# pca20020_sheet6_environment_sensors.net
KiCad netlist of a schematic drawn in Altium Designer
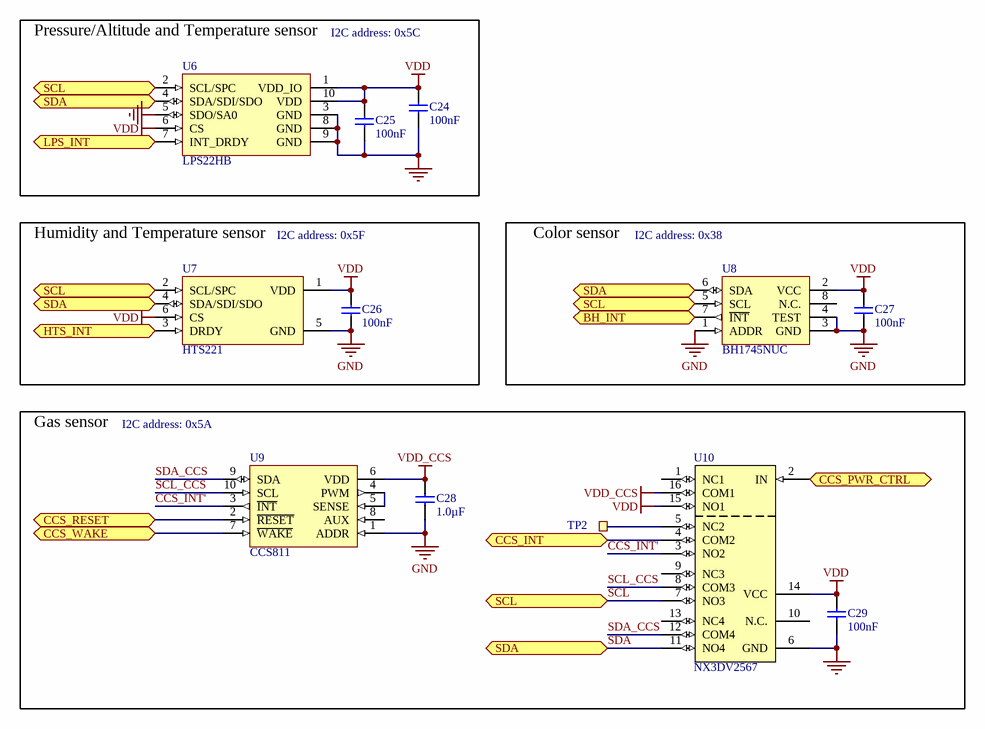
[diagram p0: pca20020_sheet6_environment_sensors.SchDoc]

(export (version "E")
  (design (tool "Eeschema 10.0.6"))
  (components
    (comp (ref "C24")
      (value "100nF")
      (footprint "CAPC1005X04L")
      (description "Capacitor, X7R, ±10%")
      (fields (field (name "PART NUMBER") "C0402-100n") (field (name "PUBLISHER") "Nordic Semiconductor"))
      (libsource (lib "Nordic Passive DB") (part "CAP"))
    )
    (comp (ref "C25")
      (value "100nF")
      (footprint "CAPC1005X04L")
      (description "Capacitor, X7R, ±10%")
      (fields (field (name "PART NUMBER") "C0402-100n") (field (name "PUBLISHER") "Nordic Semiconductor"))
      (libsource (lib "Nordic Passive DB") (part "CAP"))
    )
    (comp (ref "C26")
      (value "100nF")
      (footprint "CAPC1005X04L")
      (description "Capacitor, X7R, ±10%")
      (fields (field (name "PART NUMBER") "C0402-100n") (field (name "PUBLISHER") "Nordic Semiconductor"))
      (libsource (lib "Nordic Passive DB") (part "CAP"))
    )
    (comp (ref "C27")
      (value "100nF")
      (footprint "CAPC1005X04L")
      (description "Capacitor, X7R, ±10%")
      (fields (field (name "PART NUMBER") "C0402-100n") (field (name "PUBLISHER") "Nordic Semiconductor"))
      (libsource (lib "Nordic Passive DB") (part "CAP"))
    )
    (comp (ref "C28")
      (value "1.0µF")
      (footprint "CAPC1005X04L")
      (description "Capacitor, X5R, ±5%, 6.3V")
      (fields (field (name "PART NUMBER") "C0402-1µ0") (field (name "PUBLISHER") "Nordic Semiconductor"))
      (libsource (lib "Nordic Passive DB") (part "CAP"))
    )
    (comp (ref "C29")
      (value "100nF")
      (footprint "CAPC1005X04L")
      (description "Capacitor, X7R, ±10%")
      (fields (field (name "PART NUMBER") "C0402-100n") (field (name "PUBLISHER") "Nordic Semiconductor"))
      (libsource (lib "Nordic Passive DB") (part "CAP"))
    )
    (comp (ref "TP2")
      (value "TP")
      (footprint "TESTPAD-TH")
      (description "Testpoint, through hole")
      (fields (field (name "PART NUMBER") "Testpoint TH") (field (name "PUBLISHER") "Nordic Semiconductor"))
      (libsource (lib "Nordic Passive DB") (part "TESTPAD"))
    )
    (comp (ref "U6")
      (value "LPS22HB")
      (footprint "LGA50P200X200X80-10N")
      (description "MEMS nano pressure sensor: 260-1260 hPa absolute digital output barometer")
      (fields
        (field (name "MANUFACTURER") "STMicroelectronics")
        (field (name "PUBLISHER") "Nordic Semiconductor")
      )
      (libsource (lib "Nordic Active DB") (part "LPS22HB"))
    )
    (comp (ref "U7")
      (value "HTS221")
      (footprint "HLGA100P200X200X100-6N")
      (description "Capacitive digital sensor for relative humidity and temperature")
      (fields
        (field (name "MANUFACTURER") "STMicroelectronics")
        (field (name "PUBLISHER") "Nordic Semiconductor")
      )
      (libsource (lib "Nordic Active DB") (part "HTS221"))
    )
    (comp (ref "U8")
      (value "BH1745NUC")
      (footprint "WSON50P210X210X60_HS-9N")
      (description "Digital 16bit Serial Output Type Color Sensor IC")
      (fields
        (field (name "MANUFACTURER") "Rohm Semiconductor")
        (field (name "PUBLISHER") "Nordic Semiconductor")
      )
      (libsource (lib "Nordic Active DB") (part "BH1745NUC"))
    )
    (comp (ref "U9")
      (value "CCS811")
      (footprint "LGA60P270X400X110_HS-11N")
      (description "Ultra-low power digital gas sensor for monitoring indoor air quality")
      (fields
        (field (name "MANUFACTURER") "Cambridge CMOS Sensors")
        (field (name "PUBLISHER") "Nordic Semiconductor")
      )
      (libsource (lib "Nordic Active DB") (part "CCS811"))
    )
    (comp (ref "U10")
      (value "NX3DV2567")
      (footprint "XQFN40P180X260X50-16N")
      (description "Low-ohmic four-pole double-throw analog switch")
      (fields
        (field (name "PART NUMBER") "NX3DV2567GU")
        (field (name "MANUFACTURER") "NXP Semiconductors")
        (field (name "PUBLISHER") "Nordic Semiconductor")
      )
      (libsource (lib "Nordic Active DB") (part "NX3DV2567"))
    )
  )
  (nets
    (net (code "1") (name "/BH_INT") (class "Default")
      (node (ref "U8") (pin "7") (pinfunction "~{INT}_7") (pintype "output"))
    )
    (net (code "2") (name "/CCS_INT") (class "Default")
      (node (ref "U10") (pin "4") (pinfunction "COM2_4") (pintype "bidirectional"))
    )
    (net (code "3") (name "/CCS_INT'") (class "Default")
      (node (ref "U10") (pin "3") (pinfunction "NO2_3") (pintype "bidirectional"))
      (node (ref "U9") (pin "3") (pinfunction "~{INT}_3") (pintype "output"))
    )
    (net (code "4") (name "/CCS_PWR_CTRL") (class "Default")
      (node (ref "U10") (pin "2") (pinfunction "IN_2") (pintype "input"))
    )
    (net (code "5") (name "/CCS_RESET") (class "Default")
      (node (ref "U9") (pin "2") (pinfunction "~{RESET}_2") (pintype "input"))
    )
    (net (code "6") (name "/CCS_WAKE") (class "Default")
      (node (ref "U9") (pin "7") (pinfunction "~{WAKE}_7") (pintype "input"))
    )
    (net (code "7") (name "/HTS_INT") (class "Default")
      (node (ref "U7") (pin "3") (pinfunction "DRDY_3") (pintype "input"))
    )
    (net (code "8") (name "/LPS_INT") (class "Default")
      (node (ref "U6") (pin "7") (pinfunction "INT_DRDY_7") (pintype "input"))
    )
    (net (code "9") (name "/SCL") (class "Default")
      (node (ref "U10") (pin "7") (pinfunction "NO3_7") (pintype "bidirectional"))
      (node (ref "U6") (pin "2") (pinfunction "SCL/SPC_2") (pintype "input"))
      (node (ref "U7") (pin "2") (pinfunction "SCL/SPC_2") (pintype "input"))
      (node (ref "U8") (pin "5") (pinfunction "SCL_5") (pintype "input"))
    )
    (net (code "10") (name "/SCL_CCS") (class "Default")
      (node (ref "U10") (pin "8") (pinfunction "COM3_8") (pintype "bidirectional"))
      (node (ref "U9") (pin "10") (pinfunction "SCL_10") (pintype "input"))
    )
    (net (code "11") (name "/SDA") (class "Default")
      (node (ref "U10") (pin "11") (pinfunction "NO4_11") (pintype "bidirectional"))
      (node (ref "U6") (pin "4") (pinfunction "SDA/SDI/SDO_4") (pintype "bidirectional"))
      (node (ref "U7") (pin "4") (pinfunction "SDA/SDI/SDO_4") (pintype "bidirectional"))
      (node (ref "U8") (pin "6") (pinfunction "SDA_6") (pintype "bidirectional"))
    )
    (net (code "12") (name "/SDA_CCS") (class "Default")
      (node (ref "U10") (pin "12") (pinfunction "COM4_12") (pintype "bidirectional"))
      (node (ref "U9") (pin "9") (pinfunction "SDA_9") (pintype "bidirectional"))
    )
    (net (code "13") (name "GND") (class "Default")
      (node (ref "C24") (pin "1") (pinfunction "1_1") (pintype "passive"))
      (node (ref "C25") (pin "1") (pinfunction "1_1") (pintype "passive"))
      (node (ref "C26") (pin "1") (pinfunction "1_1") (pintype "passive"))
      (node (ref "C27") (pin "1") (pinfunction "1_1") (pintype "passive"))
      (node (ref "C28") (pin "1") (pinfunction "1_1") (pintype "passive"))
      (node (ref "C29") (pin "1") (pinfunction "1_1") (pintype "passive"))
      (node (ref "U10") (pin "6") (pinfunction "GND_6") (pintype "power_in"))
      (node (ref "U6") (pin "3") (pinfunction "GND_3") (pintype "power_in"))
      (node (ref "U6") (pin "5") (pinfunction "SDO/SA0_5") (pintype "bidirectional"))
      (node (ref "U6") (pin "8") (pinfunction "GND_8") (pintype "power_in"))
      (node (ref "U6") (pin "9") (pinfunction "GND_9") (pintype "power_in"))
      (node (ref "U7") (pin "5") (pinfunction "GND_5") (pintype "power_in"))
      (node (ref "U8") (pin "1") (pinfunction "ADDR_1") (pintype "input"))
      (node (ref "U8") (pin "3") (pinfunction "GND_3") (pintype "power_in"))
      (node (ref "U8") (pin "4") (pinfunction "TEST_4") (pintype "passive"))
      (node (ref "U8") (pin "9") (pinfunction "GND_9") (pintype "power_in"))
      (node (ref "U9") (pin "1") (pinfunction "ADDR_1") (pintype "input"))
      (node (ref "U9") (pin "11") (pinfunction "GND_11") (pintype "power_in"))
    )
    (net (code "14") (name "Net-(U9-PWM)") (class "Default")
      (node (ref "U9") (pin "4") (pinfunction "PWM_4") (pintype "output"))
      (node (ref "U9") (pin "5") (pinfunction "SENSE_5") (pintype "input"))
    )
    (net (code "15") (name "Net-(U10-NC2)") (class "Default")
      (node (ref "TP2") (pin "1") (pinfunction "1_1") (pintype "passive"))
      (node (ref "U10") (pin "5") (pinfunction "NC2_5") (pintype "bidirectional"))
    )
    (net (code "16") (name "VDD") (class "Default")
      (node (ref "C24") (pin "2") (pinfunction "2_2") (pintype "passive"))
      (node (ref "C25") (pin "2") (pinfunction "2_2") (pintype "passive"))
      (node (ref "C26") (pin "2") (pinfunction "2_2") (pintype "passive"))
      (node (ref "C27") (pin "2") (pinfunction "2_2") (pintype "passive"))
      (node (ref "C29") (pin "2") (pinfunction "2_2") (pintype "passive"))
      (node (ref "U10") (pin "14") (pinfunction "VCC_14") (pintype "power_in"))
      (node (ref "U10") (pin "15") (pinfunction "NO1_15") (pintype "bidirectional"))
      (node (ref "U6") (pin "1") (pinfunction "VDD_IO_1") (pintype "power_in"))
      (node (ref "U6") (pin "10") (pinfunction "VDD_10") (pintype "power_in"))
      (node (ref "U6") (pin "6") (pinfunction "CS_6") (pintype "input"))
      (node (ref "U7") (pin "1") (pinfunction "VDD_1") (pintype "power_in"))
      (node (ref "U7") (pin "6") (pinfunction "CS_6") (pintype "input"))
      (node (ref "U8") (pin "2") (pinfunction "VCC_2") (pintype "power_in"))
    )
    (net (code "17") (name "VDD_CCS") (class "Default")
      (node (ref "C28") (pin "2") (pinfunction "2_2") (pintype "passive"))
      (node (ref "U10") (pin "16") (pinfunction "COM1_16") (pintype "bidirectional"))
      (node (ref "U9") (pin "6") (pinfunction "VDD_6") (pintype "power_in"))
    )
    (net (code "18") (name "unconnected-(U8-N.C.-Pad8)") (class "Default")
      (node (ref "U8") (pin "8") (pinfunction "N.C._8") (pintype "passive"))
    )
    (net (code "19") (name "unconnected-(U9-AUX-Pad8)") (class "Default")
      (node (ref "U9") (pin "8") (pinfunction "AUX_8") (pintype "input"))
    )
    (net (code "20") (name "unconnected-(U10-N.C.-Pad10)") (class "Default")
      (node (ref "U10") (pin "10") (pinfunction "N.C._10") (pintype "passive"))
    )
    (net (code "21") (name "unconnected-(U10-NC1-Pad1)") (class "Default")
      (node (ref "U10") (pin "1") (pinfunction "NC1_1") (pintype "bidirectional"))
    )
    (net (code "22") (name "unconnected-(U10-NC3-Pad9)") (class "Default")
      (node (ref "U10") (pin "9") (pinfunction "NC3_9") (pintype "bidirectional"))
    )
    (net (code "23") (name "unconnected-(U10-NC4-Pad13)") (class "Default")
      (node (ref "U10") (pin "13") (pinfunction "NC4_13") (pintype "bidirectional"))
    )
  )
)
